# SX1257.net
KiCad netlist of a schematic drawn in Altium Designer
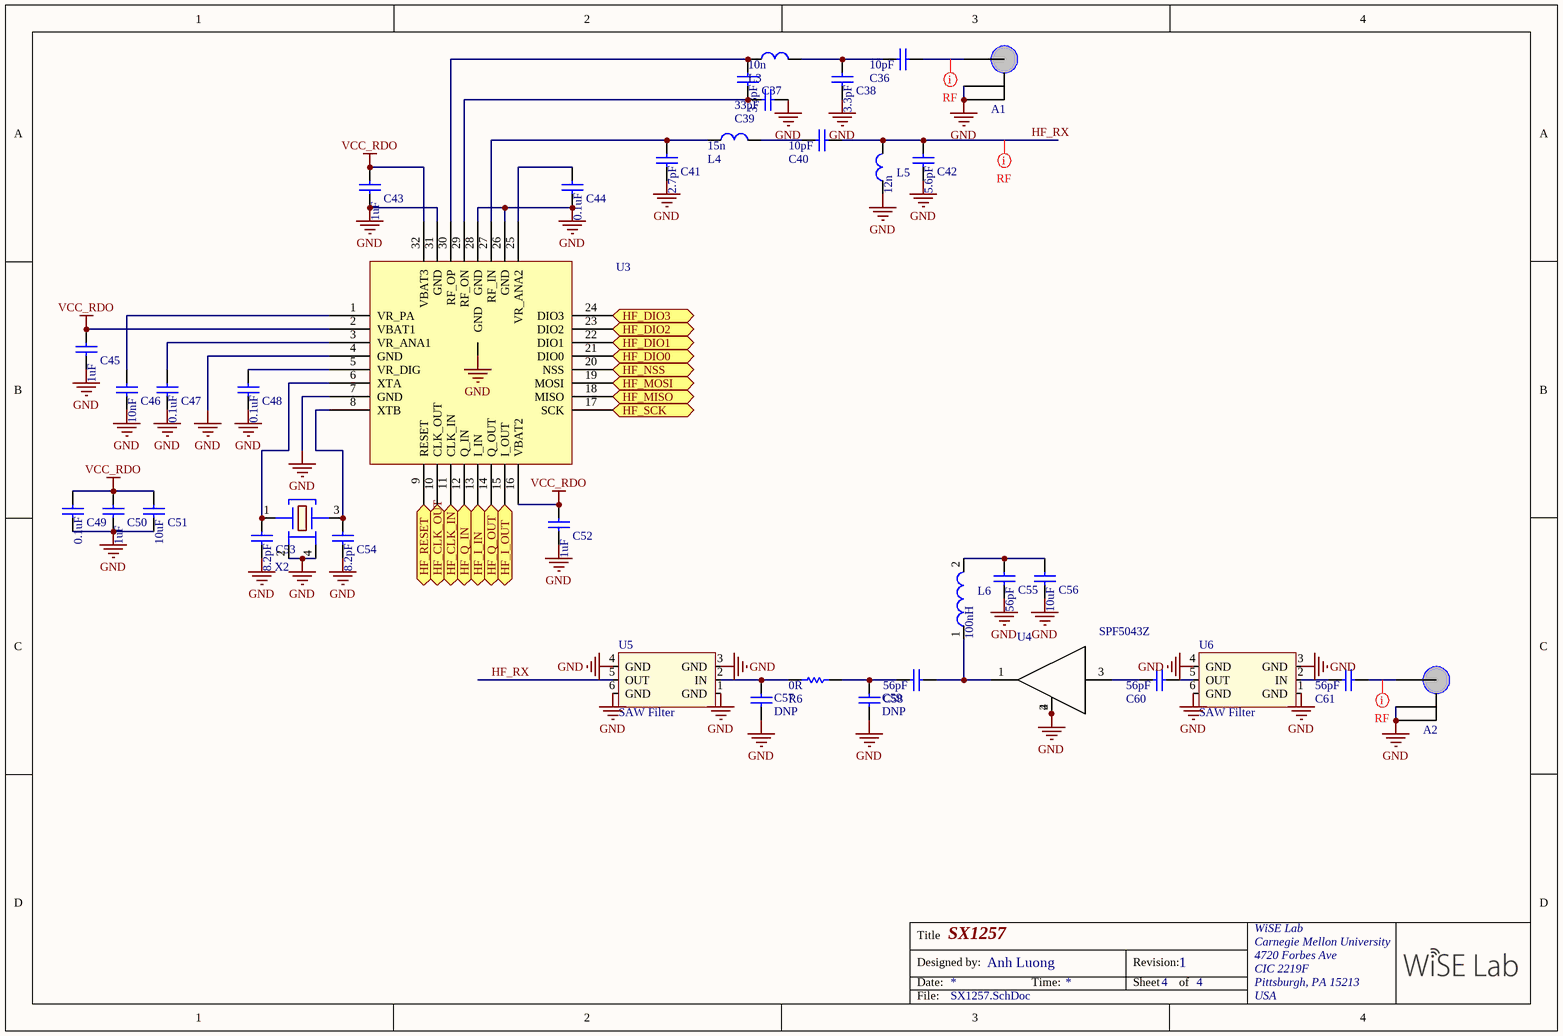
[diagram p0: SX1257.SchDoc]

(export (version "E")
  (design (tool "Eeschema 10.0.6"))
  (components
    (comp (ref "A1")
      (value "U.FL-R-SMT(01)")
      (footprint "U.FL-R-SMT-1")
      (description "CONN UMC JACK STR 50 OHM SMD")
      (fields (field (name "MANUFACTURER") "Hirose Electric Co Ltd"))
      (libsource (lib "Connectors") (part "U.FL-R-SMT(01)"))
    )
    (comp (ref "A2")
      (value "U.FL-R-SMT(01)")
      (footprint "U.FL-R-SMT-1")
      (description "CONN UMC JACK STR 50 OHM SMD")
      (fields (field (name "MANUFACTURER") "Hirose Electric Co Ltd"))
      (libsource (lib "Connectors") (part "U.FL-R-SMT(01)"))
    )
    (comp (ref "C36")
      (value "GRM1555C1H100FA01D")
      (footprint "CAPC1005X04L")
      (description "CAP CER 10PF 50V C0G/NP0 0402")
      (fields
        (field (name "MANUFACTURER") "Murata Electronics North America")
        (field (name "TOLERANCE") "±1%")
      )
      (libsource (lib "Passives") (part "GRM1555C1H100FA01D"))
    )
    (comp (ref "C37")
      (value "GRM1555C1H3R3CA01D")
      (footprint "CAPC1005X04L")
      (description "CAP CER 3.3PF 50V C0G/NP0 0402")
      (fields
        (field (name "MANUFACTURER") "Murata Electronics North America")
        (field (name "TOLERANCE") "±0.25pF")
      )
      (libsource (lib "Passives") (part "GRM1555C1H3R3CA01D"))
    )
    (comp (ref "C38")
      (value "GRM1555C1H3R3CA01D")
      (footprint "CAPC1005X04L")
      (description "CAP CER 3.3PF 50V C0G/NP0 0402")
      (fields
        (field (name "MANUFACTURER") "Murata Electronics North America")
        (field (name "TOLERANCE") "±0.25pF")
      )
      (libsource (lib "Passives") (part "GRM1555C1H3R3CA01D"))
    )
    (comp (ref "C39")
      (value "GRM1555C1H330JA01D")
      (footprint "CAPC1005X04L")
      (description "CAP CER 33PF 50V C0G/NP0 0402")
      (fields
        (field (name "MANUFACTURER") "Murata Electronics North America")
        (field (name "TOLERANCE") "±5%")
      )
      (libsource (lib "Passives") (part "GRM1555C1H330JA01D"))
    )
    (comp (ref "C40")
      (value "GRM1555C1H100FA01D")
      (footprint "CAPC1005X04L")
      (description "CAP CER 10PF 50V C0G/NP0 0402")
      (fields
        (field (name "MANUFACTURER") "Murata Electronics North America")
        (field (name "TOLERANCE") "±1%")
      )
      (libsource (lib "Passives") (part "GRM1555C1H100FA01D"))
    )
    (comp (ref "C41")
      (value "GRM1555C1H2R7BA01D")
      (footprint "CAPC1005X04L")
      (description "CAP CER 2.7PF 50V C0G/NP0 0402")
      (fields
        (field (name "MANUFACTURER") "Murata Electronics North America")
        (field (name "TOLERANCE") "±0.1pF")
      )
      (libsource (lib "Passives") (part "GRM1555C1H2R7BA01D"))
    )
    (comp (ref "C42")
      (value "GRM1555C1H5R6CA01D")
      (footprint "CAPC1005X04L")
      (description "CAP CER 5.6PF 50V C0G/NP0 0402")
      (fields
        (field (name "MANUFACTURER") "Murata Electronics North America")
        (field (name "TOLERANCE") "±0.25pF")
      )
      (libsource (lib "Passives") (part "GRM1555C1H5R6CA01D"))
    )
    (comp (ref "C43")
      (value "GRM155R60J105KE19D")
      (footprint "CAPC1005X04L")
      (description "CAP CER 1UF 6.3V X5R 0402")
      (fields
        (field (name "MANUFACTURER") "Murata Electronics North America")
        (field (name "TOLERANCE") "±10%")
      )
      (libsource (lib "Passives") (part "GRM155R60J105KE19D"))
    )
    (comp (ref "C44")
      (value "GRM155R71C104KA88D")
      (footprint "CAPC1005X04L")
      (description "CAP CER 0.1UF 16V X7R 0402")
      (fields
        (field (name "MANUFACTURER") "Murata Electronics North America")
        (field (name "TOLERANCE") "±10%")
      )
      (libsource (lib "Passives") (part "GRM155R71C104KA88D"))
    )
    (comp (ref "C45")
      (value "GRM155R60J105KE19D")
      (footprint "CAPC1005X04L")
      (description "CAP CER 1UF 6.3V X5R 0402")
      (fields
        (field (name "MANUFACTURER") "Murata Electronics North America")
        (field (name "TOLERANCE") "±10%")
      )
      (libsource (lib "Passives") (part "GRM155R60J105KE19D"))
    )
    (comp (ref "C46")
      (value "GRM155R71E103KA01D")
      (footprint "CAPC1005X04L")
      (description "CAP CER 10000PF 25V X7R 0402")
      (fields
        (field (name "MANUFACTURER") "Murata Electronics North America")
        (field (name "TOLERANCE") "±10%")
      )
      (libsource (lib "Passives") (part "GRM155R71E103KA01D"))
    )
    (comp (ref "C47")
      (value "GRM155R71C104KA88D")
      (footprint "CAPC1005X04L")
      (description "CAP CER 0.1UF 16V X7R 0402")
      (fields
        (field (name "MANUFACTURER") "Murata Electronics North America")
        (field (name "TOLERANCE") "±10%")
      )
      (libsource (lib "Passives") (part "GRM155R71C104KA88D"))
    )
    (comp (ref "C48")
      (value "GRM155R71C104KA88D")
      (footprint "CAPC1005X04L")
      (description "CAP CER 0.1UF 16V X7R 0402")
      (fields
        (field (name "MANUFACTURER") "Murata Electronics North America")
        (field (name "TOLERANCE") "±10%")
      )
      (libsource (lib "Passives") (part "GRM155R71C104KA88D"))
    )
    (comp (ref "C49")
      (value "GRM155R71C104KA88D")
      (footprint "CAPC1005X04L")
      (description "CAP CER 0.1UF 16V X7R 0402")
      (fields
        (field (name "MANUFACTURER") "Murata Electronics North America")
        (field (name "TOLERANCE") "±10%")
      )
      (libsource (lib "Passives") (part "GRM155R71C104KA88D"))
    )
    (comp (ref "C50")
      (value "GRM155R60J105KE19D")
      (footprint "CAPC1005X04L")
      (description "CAP CER 1UF 6.3V X5R 0402")
      (fields
        (field (name "MANUFACTURER") "Murata Electronics North America")
        (field (name "TOLERANCE") "±10%")
      )
      (libsource (lib "Passives") (part "GRM155R60J105KE19D"))
    )
    (comp (ref "C51")
      (value "GRM155R60J106ME15D")
      (footprint "INDC1005X04L")
      (description "CAP CER 10UF 6.3V X5R 0402")
      (fields
        (field (name "MANUFACTURER") "Murata Electronics North America")
        (field (name "TOLERANCE") "±20%")
      )
      (libsource (lib "Passives") (part "GRM155R60J106ME15D"))
    )
    (comp (ref "C52")
      (value "GRM155R60J105KE19D")
      (footprint "CAPC1005X04L")
      (description "CAP CER 1UF 6.3V X5R 0402")
      (fields
        (field (name "MANUFACTURER") "Murata Electronics North America")
        (field (name "TOLERANCE") "±10%")
      )
      (libsource (lib "Passives") (part "GRM155R60J105KE19D"))
    )
    (comp (ref "C53")
      (value "GRM1555C1H8R2CA01D")
      (footprint "CAPC1005X04L")
      (description "CAP CER 8.2PF 50V C0G/NP0 0402")
      (fields
        (field (name "MANUFACTURER") "Murata Electronics North America")
        (field (name "TOLERANCE") "±0.25pF")
      )
      (libsource (lib "Passives") (part "GRM1555C1H8R2CA01D"))
    )
    (comp (ref "C54")
      (value "GRM1555C1H8R2CA01D")
      (footprint "CAPC1005X04L")
      (description "CAP CER 8.2PF 50V C0G/NP0 0402")
      (fields
        (field (name "MANUFACTURER") "Murata Electronics North America")
        (field (name "TOLERANCE") "±0.25pF")
      )
      (libsource (lib "Passives") (part "GRM1555C1H8R2CA01D"))
    )
    (comp (ref "C55")
      (value "GRM1555C1H560JA01D")
      (footprint "CAPC1005X04L")
      (description "CAP CER 56PF 50V C0G/NP0 0402")
      (fields
        (field (name "MANUFACTURER") "Murata Electronics North America")
        (field (name "TOLERANCE") "±5%")
      )
      (libsource (lib "Passives") (part "GRM1555C1H560JA01D"))
    )
    (comp (ref "C56")
      (value "GRM155R60J106ME15D")
      (footprint "INDC1005X04L")
      (description "CAP CER 10UF 6.3V X5R 0402")
      (fields
        (field (name "MANUFACTURER") "Murata Electronics North America")
        (field (name "TOLERANCE") "±20%")
      )
      (libsource (lib "Passives") (part "GRM155R60J106ME15D"))
    )
    (comp (ref "C57")
      (value "DNP")
      (footprint "CAPC1005X04L")
      (description "C_DNP")
      (libsource (lib "Passives") (part "C_DNP"))
    )
    (comp (ref "C58")
      (value "GRM1555C1H560JA01D")
      (footprint "CAPC1005X04L")
      (description "CAP CER 56PF 50V C0G/NP0 0402")
      (fields
        (field (name "MANUFACTURER") "Murata Electronics North America")
        (field (name "TOLERANCE") "±5%")
      )
      (libsource (lib "Passives") (part "GRM1555C1H560JA01D"))
    )
    (comp (ref "C59")
      (value "DNP")
      (footprint "CAPC1005X04L")
      (description "C_DNP")
      (libsource (lib "Passives") (part "C_DNP"))
    )
    (comp (ref "C60")
      (value "GRM1555C1H560JA01D")
      (footprint "CAPC1005X04L")
      (description "CAP CER 56PF 50V C0G/NP0 0402")
      (fields
        (field (name "MANUFACTURER") "Murata Electronics North America")
        (field (name "TOLERANCE") "±5%")
      )
      (libsource (lib "Passives") (part "GRM1555C1H560JA01D"))
    )
    (comp (ref "C61")
      (value "GRM1555C1H560JA01D")
      (footprint "CAPC1005X04L")
      (description "CAP CER 56PF 50V C0G/NP0 0402")
      (fields
        (field (name "MANUFACTURER") "Murata Electronics North America")
        (field (name "TOLERANCE") "±5%")
      )
      (libsource (lib "Passives") (part "GRM1555C1H560JA01D"))
    )
    (comp (ref "L3")
      (value "LQG15HS10NJ02D")
      (footprint "INDC1005X04L")
      (description "FIXED IND 10NH 500MA 260 MOHM")
      (fields
        (field (name "MANUFACTURER") "Murata Electronics North America")
        (field (name "TOLERANCE") "±5%")
      )
      (libsource (lib "Passives") (part "LQG15HS10NJ02D"))
    )
    (comp (ref "L4")
      (value "LQG15HS15NJ02D")
      (footprint "INDC1005X04L")
      (description "FIXED IND 15NH 450MA 320 MOHM")
      (fields
        (field (name "MANUFACTURER") "Murata Electronics North America")
        (field (name "TOLERANCE") "±5%")
      )
      (libsource (lib "Passives") (part "LQG15HS15NJ02D"))
    )
    (comp (ref "L5")
      (value "LQG15HN12NJ02D")
      (footprint "INDC1005X04L")
      (description "FIXED IND 12NH 400MA 410 MOHM")
      (fields
        (field (name "MANUFACTURER") "Murata Electronics North America")
        (field (name "TOLERANCE") "±5%")
      )
      (libsource (lib "Passives") (part "LQG15HN12NJ02D"))
    )
    (comp (ref "L6")
      (value "LQG15HSR10J02D")
      (footprint "INDC1005X04L")
      (description "FIXED IND 100NH 200MA 1.25 OHM")
      (fields
        (field (name "MANUFACTURER") "Murata Electronics North America")
        (field (name "TOLERANCE") "±5%")
      )
      (libsource (lib "Passives") (part "LQG15HSR10J02D"))
    )
    (comp (ref "R6")
      (value "PMR01ZZPJ000")
      (footprint "RESC1005X04N")
      (description "RES SMD 0 OHM JUMPER 1/5W 0402")
      (fields (field (name "MANUFACTURER") "Rohm Semiconductor") (field (name "TOLERANCE") "Jumper"))
      (libsource (lib "Passives") (part "PMR01ZZPJ000"))
    )
    (comp (ref "U3")
      (value "SX1257IWLTRT")
      (footprint "QFN50P500X500X80_HS-33N")
      (description "IC RF TXRX 802.15.4 32WFQFN")
      (fields (field (name "MANUFACTURER") "Semtech Corporation"))
      (libsource (lib "RFIC") (part "SX1257IWLTRT"))
    )
    (comp (ref "U4")
      (value "SPF5043Z")
      (footprint "SOT-343")
      (description "SPF5043Z; Low Noise Amplifier; RFMD")
      (fields (field (name "MANUFACTURER") "RFMD"))
      (libsource (lib "RFIC") (part "SPF5043Z"))
    )
    (comp (ref "U5")
      (value "SAW Filter")
      (footprint "DCC6C_3.0x3.0mm")
      (description "SAW Filter - Bandpass - TEMEX type")
      (libsource (lib "RFIC") (part "SAW Filter"))
    )
    (comp (ref "U6")
      (value "SAW Filter")
      (footprint "DCC6C_3.0x3.0mm")
      (description "SAW Filter - Bandpass - TEMEX type")
      (libsource (lib "RFIC") (part "SAW Filter"))
    )
    (comp (ref "X2")
      (value "ABM11-36.000MHZ-D2X-T3")
      (footprint "2.0x1.6x0.59mmXTAL")
      (description "CRYSTAL 36.0000MHZ 10PF SMD")
      (fields (field (name "MANUFACTURER") "Abracon LLC"))
      (libsource (lib "OSC") (part "ABM11-36.000MHZ-D2X-T3"))
    )
  )
  (nets
    (net (code "1") (name "/HF_CLK_IN") (class "Default")
      (node (ref "U3") (pin "11") (pinfunction "CLK_IN_11") (pintype "passive"))
    )
    (net (code "2") (name "/HF_CLK_OUT") (class "Default")
      (node (ref "U3") (pin "10") (pinfunction "CLK_OUT_10") (pintype "passive"))
    )
    (net (code "3") (name "/HF_DIO0") (class "Default")
      (node (ref "U3") (pin "21") (pinfunction "DIO0_21") (pintype "passive"))
    )
    (net (code "4") (name "/HF_DIO1") (class "Default")
      (node (ref "U3") (pin "22") (pinfunction "DIO1_22") (pintype "passive"))
    )
    (net (code "5") (name "/HF_DIO2") (class "Default")
      (node (ref "U3") (pin "23") (pinfunction "DIO2_23") (pintype "passive"))
    )
    (net (code "6") (name "/HF_DIO3") (class "Default")
      (node (ref "U3") (pin "24") (pinfunction "DIO3_24") (pintype "passive"))
    )
    (net (code "7") (name "/HF_I_IN") (class "Default")
      (node (ref "U3") (pin "13") (pinfunction "I_IN_13") (pintype "passive"))
    )
    (net (code "8") (name "/HF_I_OUT") (class "Default")
      (node (ref "U3") (pin "15") (pinfunction "I_OUT_15") (pintype "passive"))
    )
    (net (code "9") (name "/HF_MISO") (class "Default")
      (node (ref "U3") (pin "18") (pinfunction "MISO_18") (pintype "passive"))
    )
    (net (code "10") (name "/HF_MOSI") (class "Default")
      (node (ref "U3") (pin "19") (pinfunction "MOSI_19") (pintype "passive"))
    )
    (net (code "11") (name "/HF_NSS") (class "Default")
      (node (ref "U3") (pin "20") (pinfunction "NSS_20") (pintype "passive"))
    )
    (net (code "12") (name "/HF_Q_IN") (class "Default")
      (node (ref "U3") (pin "12") (pinfunction "Q_IN_12") (pintype "passive"))
    )
    (net (code "13") (name "/HF_Q_OUT") (class "Default")
      (node (ref "U3") (pin "14") (pinfunction "Q_OUT_14") (pintype "passive"))
    )
    (net (code "14") (name "/HF_RESET") (class "Default")
      (node (ref "U3") (pin "9") (pinfunction "RESET_9") (pintype "passive"))
    )
    (net (code "15") (name "/HF_RX") (class "Default")
      (node (ref "C40") (pin "2") (pinfunction "2_2") (pintype "passive"))
      (node (ref "C42") (pin "2") (pinfunction "2_2") (pintype "passive"))
      (node (ref "L5") (pin "2") (pinfunction "2_2") (pintype "passive"))
      (node (ref "U5") (pin "5") (pinfunction "OUT_5") (pintype "passive"))
    )
    (net (code "16") (name "/HF_SCK") (class "Default")
      (node (ref "U3") (pin "17") (pinfunction "SCK_17") (pintype "passive"))
    )
    (net (code "17") (name "GND") (class "Default")
      (node (ref "A1") (pin "2") (pinfunction "2_2") (pintype "passive"))
      (node (ref "A1") (pin "3") (pinfunction "3_3") (pintype "passive"))
      (node (ref "A2") (pin "2") (pinfunction "2_2") (pintype "passive"))
      (node (ref "A2") (pin "3") (pinfunction "3_3") (pintype "passive"))
      (node (ref "C38") (pin "1") (pinfunction "1_1") (pintype "passive"))
      (node (ref "C39") (pin "2") (pinfunction "2_2") (pintype "passive"))
      (node (ref "C41") (pin "1") (pinfunction "1_1") (pintype "passive"))
      (node (ref "C42") (pin "1") (pinfunction "1_1") (pintype "passive"))
      (node (ref "C43") (pin "1") (pinfunction "1_1") (pintype "passive"))
      (node (ref "C44") (pin "1") (pinfunction "1_1") (pintype "passive"))
      (node (ref "C45") (pin "1") (pinfunction "1_1") (pintype "passive"))
      (node (ref "C46") (pin "1") (pinfunction "1_1") (pintype "passive"))
      (node (ref "C47") (pin "1") (pinfunction "1_1") (pintype "passive"))
      (node (ref "C48") (pin "1") (pinfunction "1_1") (pintype "passive"))
      (node (ref "C49") (pin "1") (pinfunction "1_1") (pintype "passive"))
      (node (ref "C50") (pin "1") (pinfunction "1_1") (pintype "passive"))
      (node (ref "C51") (pin "1") (pinfunction "1_1") (pintype "passive"))
      (node (ref "C52") (pin "1") (pinfunction "1_1") (pintype "passive"))
      (node (ref "C53") (pin "1") (pinfunction "1_1") (pintype "passive"))
      (node (ref "C54") (pin "1") (pinfunction "1_1") (pintype "passive"))
      (node (ref "C55") (pin "1") (pinfunction "1_1") (pintype "passive"))
      (node (ref "C56") (pin "1") (pinfunction "1_1") (pintype "passive"))
      (node (ref "C57") (pin "1") (pinfunction "1_1") (pintype "passive"))
      (node (ref "C59") (pin "1") (pinfunction "1_1") (pintype "passive"))
      (node (ref "L5") (pin "1") (pinfunction "1_1") (pintype "passive"))
      (node (ref "U3") (pin "26") (pinfunction "GND_26") (pintype "passive"))
      (node (ref "U3") (pin "28") (pinfunction "GND_28") (pintype "passive"))
      (node (ref "U3") (pin "31") (pinfunction "GND_31") (pintype "passive"))
      (node (ref "U3") (pin "33") (pinfunction "GND_33") (pintype "passive"))
      (node (ref "U3") (pin "4") (pinfunction "GND_4") (pintype "passive"))
      (node (ref "U3") (pin "7") (pinfunction "GND_7") (pintype "passive"))
      (node (ref "U4") (pin "2") (pinfunction "GND1_2") (pintype "passive"))
      (node (ref "U4") (pin "4") (pinfunction "GND2_4") (pintype "passive"))
      (node (ref "U5") (pin "1") (pinfunction "GND_1") (pintype "passive"))
      (node (ref "U5") (pin "3") (pinfunction "GND_3") (pintype "passive"))
      (node (ref "U5") (pin "4") (pinfunction "GND_4") (pintype "passive"))
      (node (ref "U5") (pin "6") (pinfunction "GND_6") (pintype "passive"))
      (node (ref "U6") (pin "1") (pinfunction "GND_1") (pintype "passive"))
      (node (ref "U6") (pin "3") (pinfunction "GND_3") (pintype "passive"))
      (node (ref "U6") (pin "4") (pinfunction "GND_4") (pintype "passive"))
      (node (ref "U6") (pin "6") (pinfunction "GND_6") (pintype "passive"))
      (node (ref "X2") (pin "2") (pinfunction "2_2") (pintype "power_in"))
      (node (ref "X2") (pin "4") (pinfunction "4_4") (pintype "power_in"))
    )
    (net (code "18") (name "Net-(A1-Pad1)") (class "Default")
      (node (ref "A1") (pin "1") (pinfunction "1_1") (pintype "passive"))
      (node (ref "C36") (pin "2") (pinfunction "2_2") (pintype "passive"))
    )
    (net (code "19") (name "Net-(A2-Pad1)") (class "Default")
      (node (ref "A2") (pin "1") (pinfunction "1_1") (pintype "passive"))
      (node (ref "C61") (pin "2") (pinfunction "2_2") (pintype "passive"))
    )
    (net (code "20") (name "Net-(C36-Pad1)") (class "Default")
      (node (ref "C36") (pin "1") (pinfunction "1_1") (pintype "passive"))
      (node (ref "C38") (pin "2") (pinfunction "2_2") (pintype "passive"))
      (node (ref "L3") (pin "2") (pinfunction "2_2") (pintype "passive"))
    )
    (net (code "21") (name "Net-(C40-Pad1)") (class "Default")
      (node (ref "C40") (pin "1") (pinfunction "1_1") (pintype "passive"))
      (node (ref "L4") (pin "2") (pinfunction "2_2") (pintype "passive"))
    )
    (net (code "22") (name "Net-(C55-Pad2)") (class "Default")
      (node (ref "C55") (pin "2") (pinfunction "2_2") (pintype "passive"))
      (node (ref "C56") (pin "2") (pinfunction "2_2") (pintype "passive"))
      (node (ref "L6") (pin "2") (pinfunction "2_2") (pintype "passive"))
    )
    (net (code "23") (name "Net-(C58-Pad1)") (class "Default")
      (node (ref "C58") (pin "1") (pinfunction "1_1") (pintype "passive"))
      (node (ref "C59") (pin "2") (pinfunction "2_2") (pintype "passive"))
      (node (ref "R6") (pin "2") (pinfunction "2_2") (pintype "passive"))
    )
    (net (code "24") (name "Net-(U3-RF_IN)") (class "Default")
      (node (ref "C41") (pin "2") (pinfunction "2_2") (pintype "passive"))
      (node (ref "L4") (pin "1") (pinfunction "1_1") (pintype "passive"))
      (node (ref "U3") (pin "27") (pinfunction "RF_IN_27") (pintype "passive"))
    )
    (net (code "25") (name "Net-(U3-RF_ON)") (class "Default")
      (node (ref "C37") (pin "1") (pinfunction "1_1") (pintype "passive"))
      (node (ref "C39") (pin "1") (pinfunction "1_1") (pintype "passive"))
      (node (ref "U3") (pin "29") (pinfunction "RF_ON_29") (pintype "passive"))
    )
    (net (code "26") (name "Net-(U3-RF_OP)") (class "Default")
      (node (ref "C37") (pin "2") (pinfunction "2_2") (pintype "passive"))
      (node (ref "L3") (pin "1") (pinfunction "1_1") (pintype "passive"))
      (node (ref "U3") (pin "30") (pinfunction "RF_OP_30") (pintype "passive"))
    )
    (net (code "27") (name "Net-(U3-VR_ANA1)") (class "Default")
      (node (ref "C47") (pin "2") (pinfunction "2_2") (pintype "passive"))
      (node (ref "U3") (pin "3") (pinfunction "VR_ANA1_3") (pintype "passive"))
    )
    (net (code "28") (name "Net-(U3-VR_ANA2)") (class "Default")
      (node (ref "C44") (pin "2") (pinfunction "2_2") (pintype "passive"))
      (node (ref "U3") (pin "25") (pinfunction "VR_ANA2_25") (pintype "passive"))
    )
    (net (code "29") (name "Net-(U3-VR_DIG)") (class "Default")
      (node (ref "C48") (pin "2") (pinfunction "2_2") (pintype "passive"))
      (node (ref "U3") (pin "5") (pinfunction "VR_DIG_5") (pintype "passive"))
    )
    (net (code "30") (name "Net-(U3-VR_PA)") (class "Default")
      (node (ref "C46") (pin "2") (pinfunction "2_2") (pintype "passive"))
      (node (ref "U3") (pin "1") (pinfunction "VR_PA_1") (pintype "passive"))
    )
    (net (code "31") (name "Net-(U3-XTA)") (class "Default")
      (node (ref "C53") (pin "2") (pinfunction "2_2") (pintype "passive"))
      (node (ref "U3") (pin "6") (pinfunction "XTA_6") (pintype "passive"))
      (node (ref "X2") (pin "1") (pinfunction "1_1") (pintype "passive"))
    )
    (net (code "32") (name "Net-(U3-XTB)") (class "Default")
      (node (ref "C54") (pin "2") (pinfunction "2_2") (pintype "passive"))
      (node (ref "U3") (pin "8") (pinfunction "XTB_8") (pintype "passive"))
      (node (ref "X2") (pin "3") (pinfunction "3_3") (pintype "passive"))
    )
    (net (code "33") (name "Net-(U4-IN)") (class "Default")
      (node (ref "C60") (pin "1") (pinfunction "1_1") (pintype "passive"))
      (node (ref "U4") (pin "3") (pinfunction "IN_3") (pintype "passive"))
    )
    (net (code "34") (name "Net-(U4-OUT)") (class "Default")
      (node (ref "C58") (pin "2") (pinfunction "2_2") (pintype "passive"))
      (node (ref "L6") (pin "1") (pinfunction "1_1") (pintype "passive"))
      (node (ref "U4") (pin "1") (pinfunction "OUT_1") (pintype "passive"))
    )
    (net (code "35") (name "Net-(U5-IN)") (class "Default")
      (node (ref "C57") (pin "2") (pinfunction "2_2") (pintype "passive"))
      (node (ref "R6") (pin "1") (pinfunction "1_1") (pintype "passive"))
      (node (ref "U5") (pin "2") (pinfunction "IN_2") (pintype "passive"))
    )
    (net (code "36") (name "Net-(U6-IN)") (class "Default")
      (node (ref "C61") (pin "1") (pinfunction "1_1") (pintype "passive"))
      (node (ref "U6") (pin "2") (pinfunction "IN_2") (pintype "passive"))
    )
    (net (code "37") (name "Net-(U6-OUT)") (class "Default")
      (node (ref "C60") (pin "2") (pinfunction "2_2") (pintype "passive"))
      (node (ref "U6") (pin "5") (pinfunction "OUT_5") (pintype "passive"))
    )
    (net (code "38") (name "VCC_RDO") (class "Default")
      (node (ref "C43") (pin "2") (pinfunction "2_2") (pintype "passive"))
      (node (ref "C45") (pin "2") (pinfunction "2_2") (pintype "passive"))
      (node (ref "C49") (pin "2") (pinfunction "2_2") (pintype "passive"))
      (node (ref "C50") (pin "2") (pinfunction "2_2") (pintype "passive"))
      (node (ref "C51") (pin "2") (pinfunction "2_2") (pintype "passive"))
      (node (ref "C52") (pin "2") (pinfunction "2_2") (pintype "passive"))
      (node (ref "U3") (pin "16") (pinfunction "VBAT2_16") (pintype "passive"))
      (node (ref "U3") (pin "2") (pinfunction "VBAT1_2") (pintype "passive"))
      (node (ref "U3") (pin "32") (pinfunction "VBAT3_32") (pintype "passive"))
    )
  )
)
